# cerebro5_8.net
KiCad netlist of a schematic drawn in EAGLE
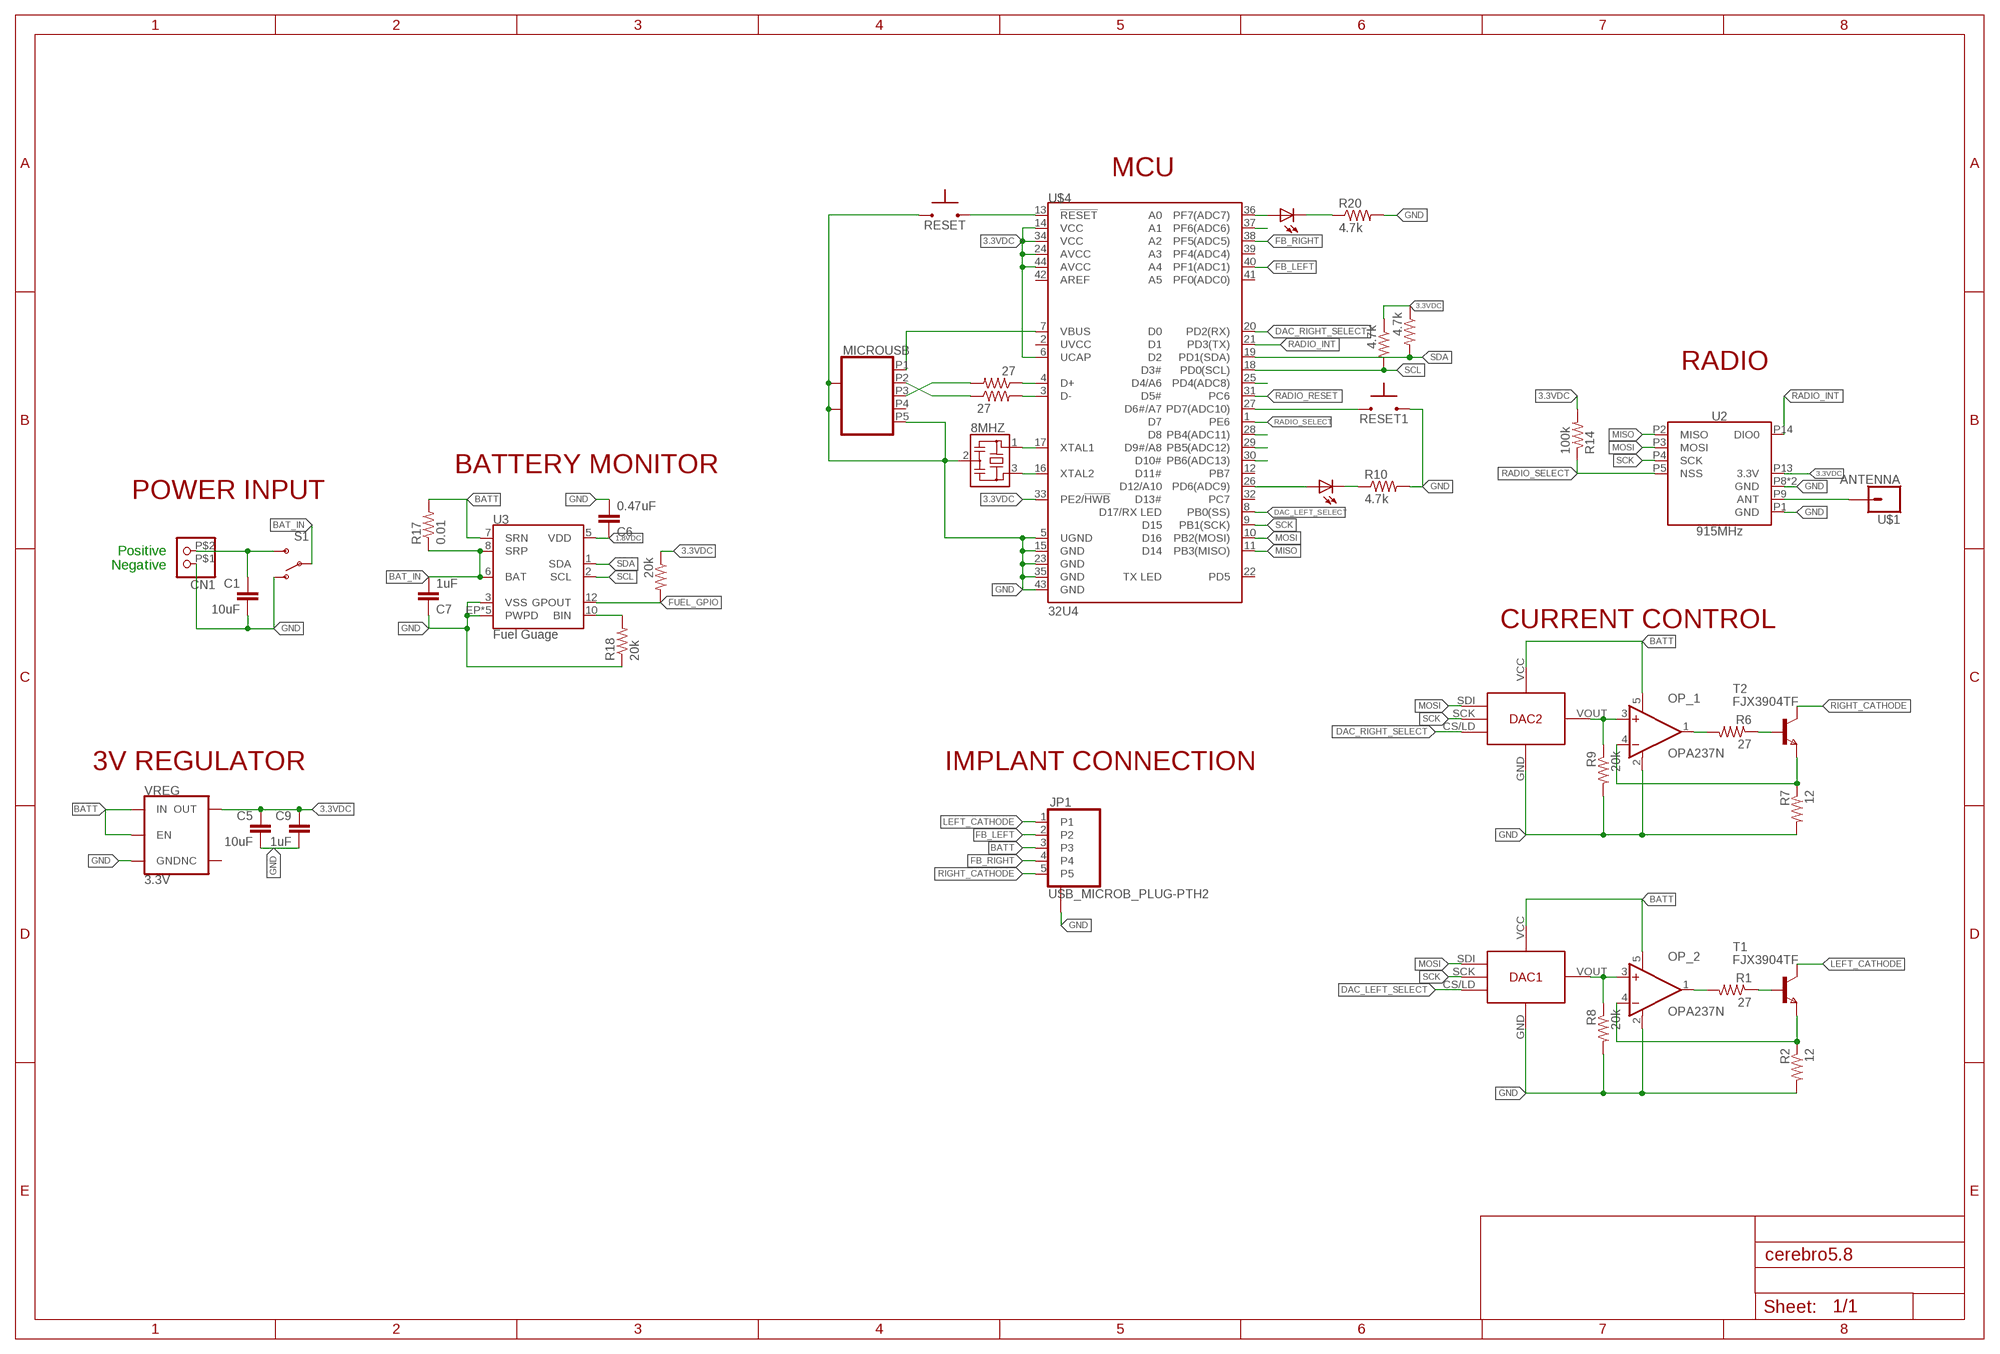
[diagram p0: schematic, sheet 1]

(export (version "E")
  (design (tool "Eeschema 10.0.6"))
  (components
    (comp (ref "8MHZ")
      (value "RESONATOR_CSTCE_V")
      (footprint "eagle-import:CSTCE_V")
      (libsource (lib "eagle-import") (part "RESONATOR_CSTCE_V"))
    )
    (comp (ref "C1")
      (value "10uF")
      (footprint "eagle-import:0805")
      (libsource (lib "eagle-import") (part "10UF-0805-10V-10%"))
    )
    (comp (ref "C5")
      (value "10uF")
      (footprint "eagle-import:0805")
      (libsource (lib "eagle-import") (part "10UF-0805-10V-10%"))
    )
    (comp (ref "C6")
      (value "0.47uF")
      (footprint "eagle-import:0805")
      (libsource (lib "eagle-import") (part "10UF-0805-10V-10%"))
    )
    (comp (ref "C7")
      (value "1uF")
      (footprint "eagle-import:0805")
      (libsource (lib "eagle-import") (part "10UF-0805-10V-10%"))
    )
    (comp (ref "C9")
      (value "1uF")
      (footprint "eagle-import:0805")
      (libsource (lib "eagle-import") (part "10UF-0805-10V-10%"))
    )
    (comp (ref "CN1")
      (value "JST_2PINMICRO")
      (footprint "eagle-import:MICRO_LOCK_2PIN")
      (libsource (lib "eagle-import") (part "JST_2PINMICRO"))
    )
    (comp (ref "DAC1")
      (value "DAC")
      (footprint "eagle-import:SC-70")
      (libsource (lib "eagle-import") (part "DAC_LTC2630"))
    )
    (comp (ref "DAC2")
      (value "DAC")
      (footprint "eagle-import:SC-70")
      (libsource (lib "eagle-import") (part "DAC_LTC2630"))
    )
    (comp (ref "INDICATOR_LED1")
      (value "YLW")
      (footprint "eagle-import:CHIP-LED0603")
      (libsource (lib "eagle-import") (part "LEDCHIP-LED0603"))
    )
    (comp (ref "INDICATOR_LED2")
      (value "GRN")
      (footprint "eagle-import:CHIP-LED0603")
      (libsource (lib "eagle-import") (part "LEDCHIP-LED0603"))
    )
    (comp (ref "JP1")
      (value "USB_MICROB_PLUG-PTH2")
      (footprint "eagle-import:MICRO-B-TH")
      (libsource (lib "eagle-import") (part "USB_MICROB_PLUG-PTH2"))
    )
    (comp (ref "MICROUSB")
      (value "USB_MICRO_SOCKET_HORZ_REINFORCED")
      (footprint "eagle-import:USB_HORZ_REINFORCED_MICRO")
      (libsource (lib "eagle-import") (part "USB_MICRO_SOCKET_HORZ_REINFORCED"))
    )
    (comp (ref "OP_1")
      (value "OPA237N")
      (footprint "eagle-import:SOT23-5")
      (fields (field (name "MF") "TEXAS INSTRUMENTS") (field (name "MPN") "OPA237NA/250"))
      (libsource (lib "eagle-import") (part "OPA237N"))
    )
    (comp (ref "OP_2")
      (value "OPA237N")
      (footprint "eagle-import:SOT23-5")
      (fields (field (name "MF") "TEXAS INSTRUMENTS") (field (name "MPN") "OPA237NA/250"))
      (libsource (lib "eagle-import") (part "OPA237N"))
    )
    (comp (ref "R1")
      (value "27")
      (footprint "eagle-import:0603-RES")
      (libsource (lib "eagle-import") (part "RESISTOR0603-RES"))
    )
    (comp (ref "R2")
      (value "12")
      (footprint "eagle-import:0603-RES")
      (libsource (lib "eagle-import") (part "RESISTOR0603-RES"))
    )
    (comp (ref "R6")
      (value "27")
      (footprint "eagle-import:0603-RES")
      (libsource (lib "eagle-import") (part "RESISTOR0603-RES"))
    )
    (comp (ref "R7")
      (value "12")
      (footprint "eagle-import:0603-RES")
      (libsource (lib "eagle-import") (part "RESISTOR0603-RES"))
    )
    (comp (ref "R8")
      (value "20k")
      (footprint "eagle-import:0603-RES")
      (libsource (lib "eagle-import") (part "RESISTOR0603-RES"))
    )
    (comp (ref "R9")
      (value "20k")
      (footprint "eagle-import:0603-RES")
      (libsource (lib "eagle-import") (part "RESISTOR0603-RES"))
    )
    (comp (ref "R10")
      (value "4.7k")
      (footprint "eagle-import:0603-RES")
      (libsource (lib "eagle-import") (part "RESISTOR0603-RES"))
    )
    (comp (ref "R12")
      (value "27")
      (footprint "eagle-import:0603-RES")
      (libsource (lib "eagle-import") (part "RESISTOR0603-RES"))
    )
    (comp (ref "R13")
      (value "27")
      (footprint "eagle-import:0603-RES")
      (libsource (lib "eagle-import") (part "RESISTOR0603-RES"))
    )
    (comp (ref "R14")
      (value "100k")
      (footprint "eagle-import:0603-RES")
      (libsource (lib "eagle-import") (part "RESISTOR0603-RES"))
    )
    (comp (ref "R15")
      (value "4.7k")
      (footprint "eagle-import:0603-RES")
      (libsource (lib "eagle-import") (part "RESISTOR0603-RES"))
    )
    (comp (ref "R16")
      (value "4.7k")
      (footprint "eagle-import:0603-RES")
      (libsource (lib "eagle-import") (part "RESISTOR0603-RES"))
    )
    (comp (ref "R17")
      (value "0.01")
      (footprint "eagle-import:1206")
      (libsource (lib "eagle-import") (part "RESISTOR1206"))
    )
    (comp (ref "R18")
      (value "20k")
      (footprint "eagle-import:0603-RES")
      (libsource (lib "eagle-import") (part "RESISTOR0603-RES"))
    )
    (comp (ref "R19")
      (value "20k")
      (footprint "eagle-import:0603-RES")
      (libsource (lib "eagle-import") (part "RESISTOR0603-RES"))
    )
    (comp (ref "R20")
      (value "4.7k")
      (footprint "eagle-import:0603-RES")
      (libsource (lib "eagle-import") (part "RESISTOR0603-RES"))
    )
    (comp (ref "RESET")
      (value "SWITCH-MOMENTARY-NO")
      (footprint "eagle-import:SWITCH_MOMENTARY_XS")
      (libsource (lib "eagle-import") (part "SWITCH-MOMENTARY-NO"))
    )
    (comp (ref "RESET1")
      (value "SWITCH-MOMENTARY-NO")
      (footprint "eagle-import:SWITCH_MOMENTARY_XS")
      (libsource (lib "eagle-import") (part "SWITCH-MOMENTARY-NO"))
    )
    (comp (ref "S1")
      (value "SWITCH-SPDTREINFORCED_SMD")
      (footprint "eagle-import:SWITCH-SPDT-SMD-REINFORCED")
      (libsource (lib "eagle-import") (part "SWITCH-SPDTREINFORCED_SMD"))
    )
    (comp (ref "T1")
      (value "FJX3904TF")
      (footprint "eagle-import:SOT323")
      (fields (field (name "MPN") "DSS4160U-7"))
      (libsource (lib "eagle-import") (part "NPNSOT323"))
    )
    (comp (ref "T2")
      (value "FJX3904TF")
      (footprint "eagle-import:SOT323")
      (fields (field (name "MPN") "DSS4160U-7"))
      (libsource (lib "eagle-import") (part "NPNSOT323"))
    )
    (comp (ref "U$1")
      (value "ANTENNA")
      (footprint "eagle-import:1X01")
      (libsource (lib "eagle-import") (part "ANTENNA"))
    )
    (comp (ref "U$4")
      (value "32U4")
      (footprint "eagle-import:QFN-44-NOPAD")
      (libsource (lib "eagle-import") (part "ATMEGA32U4QFN2"))
    )
    (comp (ref "U2")
      (value "915MHz")
      (footprint "eagle-import:RFM69HCW-XXXS2")
      (libsource (lib "eagle-import") (part "RFM69HCW-915"))
    )
    (comp (ref "U3")
      (value "Fuel Guage")
      (footprint "eagle-import:PDSO-N12")
      (libsource (lib "eagle-import") (part "BQ27441-G1"))
    )
    (comp (ref "VREG")
      (value "3.3V")
      (footprint "eagle-import:SOT23-5")
      (libsource (lib "eagle-import") (part "V_REG_AP2112K-3.3V"))
    )
  )
  (nets
    (net (code "1") (name "1.8VDC") (class "Default")
      (node (ref "C6") (pin "1") (pinfunction "1_1") (pintype "passive"))
      (node (ref "U3") (pin "5") (pinfunction "VDD_5") (pintype "bidirectional"))
    )
    (net (code "2") (name "3.3VDC") (class "Default")
      (node (ref "C5") (pin "1") (pinfunction "1_1") (pintype "passive"))
      (node (ref "C9") (pin "1") (pinfunction "1_1") (pintype "passive"))
      (node (ref "R14") (pin "2") (pinfunction "2_2") (pintype "passive"))
      (node (ref "R15") (pin "1") (pinfunction "1_1") (pintype "passive"))
      (node (ref "R16") (pin "1") (pinfunction "1_1") (pintype "passive"))
      (node (ref "R19") (pin "1") (pinfunction "1_1") (pintype "passive"))
      (node (ref "U$4") (pin "14") (pinfunction "VCC_14") (pintype "bidirectional"))
      (node (ref "U$4") (pin "24") (pinfunction "AVCC_24") (pintype "bidirectional"))
      (node (ref "U$4") (pin "33") (pinfunction "PE2/~{HWB}_33") (pintype "bidirectional"))
      (node (ref "U$4") (pin "34") (pinfunction "VCC_34") (pintype "bidirectional"))
      (node (ref "U$4") (pin "44") (pinfunction "AVCC_44") (pintype "bidirectional"))
      (node (ref "U$4") (pin "6") (pinfunction "UCAP_6") (pintype "bidirectional"))
      (node (ref "U2") (pin "P13") (pinfunction "3.3V_P13") (pintype "power_in"))
      (node (ref "VREG") (pin "5") (pinfunction "OUT_5") (pintype "passive"))
    )
    (net (code "3") (name "BATT") (class "Default")
      (node (ref "DAC1") (pin "VCC") (pinfunction "VIN_VCC") (pintype "bidirectional"))
      (node (ref "DAC2") (pin "VCC") (pinfunction "VIN_VCC") (pintype "bidirectional"))
      (node (ref "JP1") (pin "3") (pinfunction "P3_3") (pintype "bidirectional"))
      (node (ref "OP_1") (pin "5") (pinfunction "V+_5") (pintype "power_in"))
      (node (ref "OP_2") (pin "5") (pinfunction "V+_5") (pintype "power_in"))
      (node (ref "R17") (pin "2") (pinfunction "2_2") (pintype "passive"))
      (node (ref "U3") (pin "7") (pinfunction "SRN_7") (pintype "bidirectional"))
      (node (ref "VREG") (pin "1") (pinfunction "IN_1") (pintype "input"))
      (node (ref "VREG") (pin "3") (pinfunction "EN_3") (pintype "input"))
    )
    (net (code "4") (name "BAT_IN") (class "Default")
      (node (ref "C7") (pin "2") (pinfunction "2_2") (pintype "passive"))
      (node (ref "R17") (pin "1") (pinfunction "1_1") (pintype "passive"))
      (node (ref "S1") (pin "2") (pinfunction "P_2") (pintype "passive"))
      (node (ref "U3") (pin "6") (pinfunction "BAT_6") (pintype "bidirectional"))
      (node (ref "U3") (pin "8") (pinfunction "SRP_8") (pintype "bidirectional"))
    )
    (net (code "5") (name "DAC_LEFT_SELECT") (class "Default")
      (node (ref "DAC1") (pin "CS/LD") (pinfunction "CS/LD_CS/LD") (pintype "bidirectional"))
      (node (ref "U$4") (pin "8") (pinfunction "PB0(SS)_8") (pintype "bidirectional"))
    )
    (net (code "6") (name "DAC_RIGHT_SELECT") (class "Default")
      (node (ref "DAC2") (pin "CS/LD") (pinfunction "CS/LD_CS/LD") (pintype "bidirectional"))
      (node (ref "U$4") (pin "20") (pinfunction "PD2(RX)_20") (pintype "bidirectional"))
    )
    (net (code "7") (name "FB_LEFT") (class "Default")
      (node (ref "JP1") (pin "2") (pinfunction "P2_2") (pintype "bidirectional"))
      (node (ref "U$4") (pin "40") (pinfunction "PF1(ADC1)_40") (pintype "bidirectional"))
    )
    (net (code "8") (name "FB_RIGHT") (class "Default")
      (node (ref "JP1") (pin "4") (pinfunction "P4_4") (pintype "bidirectional"))
      (node (ref "U$4") (pin "38") (pinfunction "PF5(ADC5)_38") (pintype "bidirectional"))
    )
    (net (code "9") (name "FUEL_GPIO") (class "Default")
      (node (ref "R19") (pin "2") (pinfunction "2_2") (pintype "passive"))
      (node (ref "U3") (pin "12") (pinfunction "GPOUT_12") (pintype "bidirectional"))
    )
    (net (code "10") (name "GND") (class "Default")
      (node (ref "8MHZ") (pin "2") (pinfunction "2_2") (pintype "passive"))
      (node (ref "C1") (pin "2") (pinfunction "2_2") (pintype "passive"))
      (node (ref "C5") (pin "2") (pinfunction "2_2") (pintype "passive"))
      (node (ref "C6") (pin "2") (pinfunction "2_2") (pintype "passive"))
      (node (ref "C7") (pin "1") (pinfunction "1_1") (pintype "passive"))
      (node (ref "C9") (pin "2") (pinfunction "2_2") (pintype "passive"))
      (node (ref "CN1") (pin "P$1") (pinfunction "1_P$1") (pintype "passive"))
      (node (ref "DAC1") (pin "GND") (pinfunction "GND_GND") (pintype "bidirectional"))
      (node (ref "DAC2") (pin "GND") (pinfunction "GND_GND") (pintype "bidirectional"))
      (node (ref "JP1") (pin "P$1") (pinfunction "GND_PINS_P$1") (pintype "bidirectional"))
      (node (ref "JP1") (pin "P$2") (pinfunction "GND_PINS_P$2") (pintype "bidirectional"))
      (node (ref "MICROUSB") (pin "G1") (pinfunction "P$1_G1") (pintype "bidirectional"))
      (node (ref "MICROUSB") (pin "G2") (pinfunction "P$1_G2") (pintype "bidirectional"))
      (node (ref "MICROUSB") (pin "P$1") (pinfunction "P$2_P$1") (pintype "bidirectional"))
      (node (ref "MICROUSB") (pin "P$2") (pinfunction "P$2_P$2") (pintype "bidirectional"))
      (node (ref "MICROUSB") (pin "P5") (pinfunction "P5_P5") (pintype "bidirectional"))
      (node (ref "OP_1") (pin "2") (pinfunction "V-_2") (pintype "power_in"))
      (node (ref "OP_2") (pin "2") (pinfunction "V-_2") (pintype "power_in"))
      (node (ref "R10") (pin "2") (pinfunction "2_2") (pintype "passive"))
      (node (ref "R18") (pin "1") (pinfunction "1_1") (pintype "passive"))
      (node (ref "R2") (pin "2") (pinfunction "2_2") (pintype "passive"))
      (node (ref "R20") (pin "2") (pinfunction "2_2") (pintype "passive"))
      (node (ref "R7") (pin "2") (pinfunction "2_2") (pintype "passive"))
      (node (ref "R8") (pin "2") (pinfunction "2_2") (pintype "passive"))
      (node (ref "R9") (pin "2") (pinfunction "2_2") (pintype "passive"))
      (node (ref "RESET") (pin "P$1") (pinfunction "1_P$1") (pintype "bidirectional"))
      (node (ref "RESET1") (pin "P$2") (pinfunction "2_P$2") (pintype "bidirectional"))
      (node (ref "S1") (pin "1") (pinfunction "O_1") (pintype "passive"))
      (node (ref "U$4") (pin "15") (pinfunction "GND_15") (pintype "bidirectional"))
      (node (ref "U$4") (pin "23") (pinfunction "GND_23") (pintype "bidirectional"))
      (node (ref "U$4") (pin "35") (pinfunction "GND_35") (pintype "bidirectional"))
      (node (ref "U$4") (pin "43") (pinfunction "GND_43") (pintype "bidirectional"))
      (node (ref "U$4") (pin "5") (pinfunction "UGND_5") (pintype "bidirectional"))
      (node (ref "U2") (pin "P1") (pinfunction "GND_P1") (pintype "power_in"))
      (node (ref "U2") (pin "P10") (pinfunction "GND_P10") (pintype "power_in"))
      (node (ref "U2") (pin "P8") (pinfunction "GND_P8") (pintype "power_in"))
      (node (ref "U3") (pin "3") (pinfunction "VSS_3") (pintype "bidirectional"))
      (node (ref "U3") (pin "EP") (pinfunction "PWPD_EP") (pintype "bidirectional"))
      (node (ref "U3") (pin "EP1") (pinfunction "PWPD_EP1") (pintype "bidirectional"))
      (node (ref "U3") (pin "EP2") (pinfunction "PWPD_EP2") (pintype "bidirectional"))
      (node (ref "U3") (pin "EP3") (pinfunction "PWPD_EP3") (pintype "bidirectional"))
      (node (ref "U3") (pin "EP4") (pinfunction "PWPD_EP4") (pintype "bidirectional"))
      (node (ref "VREG") (pin "2") (pinfunction "GND_2") (pintype "input"))
    )
    (net (code "11") (name "LEFT_CATHODE") (class "Default")
      (node (ref "JP1") (pin "1") (pinfunction "P1_1") (pintype "bidirectional"))
      (node (ref "T1") (pin "1") (pinfunction "C_1") (pintype "passive"))
    )
    (net (code "12") (name "MISO") (class "Default")
      (node (ref "U$4") (pin "11") (pinfunction "PB3(MISO)_11") (pintype "bidirectional"))
      (node (ref "U2") (pin "P2") (pinfunction "MISO_P2") (pintype "bidirectional"))
    )
    (net (code "13") (name "MOSI") (class "Default")
      (node (ref "DAC1") (pin "SDI") (pinfunction "SDI_SDI") (pintype "bidirectional"))
      (node (ref "DAC2") (pin "SDI") (pinfunction "SDI_SDI") (pintype "bidirectional"))
      (node (ref "U$4") (pin "10") (pinfunction "PB2(MOSI)_10") (pintype "bidirectional"))
      (node (ref "U2") (pin "P3") (pinfunction "MOSI_P3") (pintype "input"))
    )
    (net (code "14") (name "Net-(CN1-2)") (class "Default")
      (node (ref "C1") (pin "1") (pinfunction "1_1") (pintype "passive"))
      (node (ref "CN1") (pin "P$2") (pinfunction "2_P$2") (pintype "passive"))
      (node (ref "S1") (pin "3") (pinfunction "S_3") (pintype "passive"))
    )
    (net (code "15") (name "Net-(INDICATOR_LED1-PadC)") (class "Default")
      (node (ref "INDICATOR_LED1") (pin "C") (pinfunction "C_C") (pintype "passive"))
      (node (ref "R20") (pin "1") (pinfunction "1_1") (pintype "passive"))
    )
    (net (code "16") (name "Net-(INDICATOR_LED2-PadC)") (class "Default")
      (node (ref "INDICATOR_LED2") (pin "C") (pinfunction "C_C") (pintype "passive"))
      (node (ref "R10") (pin "1") (pinfunction "1_1") (pintype "passive"))
    )
    (net (code "17") (name "Net-(MICROUSB-PadP2)") (class "Default")
      (node (ref "MICROUSB") (pin "P2") (pinfunction "P2_P2") (pintype "bidirectional"))
      (node (ref "R13") (pin "1") (pinfunction "1_1") (pintype "passive"))
    )
    (net (code "18") (name "Net-(MICROUSB-PadP3)") (class "Default")
      (node (ref "MICROUSB") (pin "P3") (pinfunction "P3_P3") (pintype "bidirectional"))
      (node (ref "R12") (pin "2") (pinfunction "2_2") (pintype "passive"))
    )
    (net (code "19") (name "Net-(OP_1-+IN)") (class "Default")
      (node (ref "DAC2") (pin "VOUT") (pinfunction "VOUT_VOUT") (pintype "bidirectional"))
      (node (ref "OP_1") (pin "3") (pinfunction "+IN_3") (pintype "input"))
      (node (ref "R9") (pin "1") (pinfunction "1_1") (pintype "passive"))
    )
    (net (code "20") (name "Net-(OP_1--IN)") (class "Default")
      (node (ref "OP_1") (pin "4") (pinfunction "-IN_4") (pintype "input"))
      (node (ref "R7") (pin "1") (pinfunction "1_1") (pintype "passive"))
      (node (ref "T2") (pin "3") (pinfunction "E_3") (pintype "passive"))
    )
    (net (code "21") (name "Net-(OP_1-OUT)") (class "Default")
      (node (ref "OP_1") (pin "1") (pinfunction "OUT_1") (pintype "output"))
      (node (ref "R6") (pin "2") (pinfunction "2_2") (pintype "passive"))
    )
    (net (code "22") (name "Net-(OP_2-+IN)") (class "Default")
      (node (ref "DAC1") (pin "VOUT") (pinfunction "VOUT_VOUT") (pintype "bidirectional"))
      (node (ref "OP_2") (pin "3") (pinfunction "+IN_3") (pintype "input"))
      (node (ref "R8") (pin "1") (pinfunction "1_1") (pintype "passive"))
    )
    (net (code "23") (name "Net-(OP_2--IN)") (class "Default")
      (node (ref "OP_2") (pin "4") (pinfunction "-IN_4") (pintype "input"))
      (node (ref "R2") (pin "1") (pinfunction "1_1") (pintype "passive"))
      (node (ref "T1") (pin "3") (pinfunction "E_3") (pintype "passive"))
    )
    (net (code "24") (name "Net-(OP_2-OUT)") (class "Default")
      (node (ref "OP_2") (pin "1") (pinfunction "OUT_1") (pintype "output"))
      (node (ref "R1") (pin "2") (pinfunction "2_2") (pintype "passive"))
    )
    (net (code "25") (name "Net-(RESET-2)") (class "Default")
      (node (ref "RESET") (pin "P$2") (pinfunction "2_P$2") (pintype "bidirectional"))
      (node (ref "U$4") (pin "13") (pinfunction "~{RESET}_13") (pintype "bidirectional"))
    )
    (net (code "26") (name "Net-(RESET1-1)") (class "Default")
      (node (ref "RESET1") (pin "P$1") (pinfunction "1_P$1") (pintype "bidirectional"))
      (node (ref "U$4") (pin "27") (pinfunction "PD7(ADC10)_27") (pintype "bidirectional"))
    )
    (net (code "27") (name "Net-(T1-B)") (class "Default")
      (node (ref "R1") (pin "1") (pinfunction "1_1") (pintype "passive"))
      (node (ref "T1") (pin "2") (pinfunction "B_2") (pintype "passive"))
    )
    (net (code "28") (name "Net-(T2-B)") (class "Default")
      (node (ref "R6") (pin "1") (pinfunction "1_1") (pintype "passive"))
      (node (ref "T2") (pin "2") (pinfunction "B_2") (pintype "passive"))
    )
    (net (code "29") (name "Net-(U$4-D+)") (class "Default")
      (node (ref "R12") (pin "1") (pinfunction "1_1") (pintype "passive"))
      (node (ref "U$4") (pin "4") (pinfunction "D+_4") (pintype "bidirectional"))
    )
    (net (code "30") (name "Net-(U$4-D-)") (class "Default")
      (node (ref "R13") (pin "2") (pinfunction "2_2") (pintype "passive"))
      (node (ref "U$4") (pin "3") (pinfunction "D-_3") (pintype "bidirectional"))
    )
    (net (code "31") (name "Net-(U$4-PD6(ADC9))") (class "Default")
      (node (ref "INDICATOR_LED2") (pin "A") (pinfunction "A_A") (pintype "passive"))
      (node (ref "U$4") (pin "26") (pinfunction "PD6(ADC9)_26") (pintype "bidirectional"))
    )
    (net (code "32") (name "Net-(U$4-PF7(ADC7))") (class "Default")
      (node (ref "INDICATOR_LED1") (pin "A") (pinfunction "A_A") (pintype "passive"))
      (node (ref "U$4") (pin "36") (pinfunction "PF7(ADC7)_36") (pintype "bidirectional"))
    )
    (net (code "33") (name "Net-(U$4-VBUS)") (class "Default")
      (node (ref "MICROUSB") (pin "P1") (pinfunction "P1_P1") (pintype "bidirectional"))
      (node (ref "U$4") (pin "7") (pinfunction "VBUS_7") (pintype "bidirectional"))
    )
    (net (code "34") (name "Net-(U$4-XTAL1)") (class "Default")
      (node (ref "8MHZ") (pin "1") (pinfunction "1_1") (pintype "passive"))
      (node (ref "U$4") (pin "17") (pinfunction "XTAL1_17") (pintype "bidirectional"))
    )
    (net (code "35") (name "Net-(U$4-XTAL2)") (class "Default")
      (node (ref "8MHZ") (pin "3") (pinfunction "3_3") (pintype "passive"))
      (node (ref "U$4") (pin "16") (pinfunction "XTAL2_16") (pintype "bidirectional"))
    )
    (net (code "36") (name "Net-(U2-ANT)") (class "Default")
      (node (ref "U$1") (pin "1") (pinfunction "1_1") (pintype "passive"))
      (node (ref "U2") (pin "P9") (pinfunction "ANT_P9") (pintype "passive"))
    )
    (net (code "37") (name "Net-(U3-BIN)") (class "Default")
      (node (ref "R18") (pin "2") (pinfunction "2_2") (pintype "passive"))
      (node (ref "U3") (pin "10") (pinfunction "BIN_10") (pintype "bidirectional"))
    )
    (net (code "38") (name "RADIO_INT") (class "Default")
      (node (ref "U$4") (pin "21") (pinfunction "PD3(TX)_21") (pintype "bidirectional"))
      (node (ref "U2") (pin "P14") (pinfunction "DIO0_P14") (pintype "bidirectional"))
    )
    (net (code "39") (name "RADIO_RESET") (class "Default")
      (node (ref "U$4") (pin "31") (pinfunction "PC6_31") (pintype "bidirectional"))
    )
    (net (code "40") (name "RADIO_SELECT") (class "Default")
      (node (ref "R14") (pin "1") (pinfunction "1_1") (pintype "passive"))
      (node (ref "U$4") (pin "1") (pinfunction "PE6_1") (pintype "bidirectional"))
      (node (ref "U2") (pin "P5") (pinfunction "NSS_P5") (pintype "input"))
    )
    (net (code "41") (name "RIGHT_CATHODE") (class "Default")
      (node (ref "JP1") (pin "5") (pinfunction "P5_5") (pintype "bidirectional"))
      (node (ref "T2") (pin "1") (pinfunction "C_1") (pintype "passive"))
    )
    (net (code "42") (name "SCK") (class "Default")
      (node (ref "DAC1") (pin "SCK") (pinfunction "SCK_SCK") (pintype "bidirectional"))
      (node (ref "DAC2") (pin "SCK") (pinfunction "SCK_SCK") (pintype "bidirectional"))
      (node (ref "U$4") (pin "9") (pinfunction "PB1(SCK)_9") (pintype "bidirectional"))
      (node (ref "U2") (pin "P4") (pinfunction "SCK_P4") (pintype "input"))
    )
    (net (code "43") (name "SCL") (class "Default")
      (node (ref "R15") (pin "2") (pinfunction "2_2") (pintype "passive"))
      (node (ref "U$4") (pin "18") (pinfunction "PD0(SCL)_18") (pintype "bidirectional"))
      (node (ref "U3") (pin "2") (pinfunction "SCL_2") (pintype "bidirectional"))
    )
    (net (code "44") (name "SDA") (class "Default")
      (node (ref "R16") (pin "2") (pinfunction "2_2") (pintype "passive"))
      (node (ref "U$4") (pin "19") (pinfunction "PD1(SDA)_19") (pintype "bidirectional"))
      (node (ref "U3") (pin "1") (pinfunction "SDA_1") (pintype "bidirectional"))
    )
    (net (code "45") (name "unconnected-(MICROUSB-PadP4)") (class "Default")
      (node (ref "MICROUSB") (pin "P4") (pinfunction "P4_P4") (pintype "bidirectional"))
    )
    (net (code "46") (name "unconnected-(U$4-AREF-Pad42)") (class "Default")
      (node (ref "U$4") (pin "42") (pinfunction "AREF_42") (pintype "bidirectional"))
    )
    (net (code "47") (name "unconnected-(U$4-PB4(ADC11)-Pad28)") (class "Default")
      (node (ref "U$4") (pin "28") (pinfunction "PB4(ADC11)_28") (pintype "bidirectional"))
    )
    (net (code "48") (name "unconnected-(U$4-PB5(ADC12)-Pad29)") (class "Default")
      (node (ref "U$4") (pin "29") (pinfunction "PB5(ADC12)_29") (pintype "bidirectional"))
    )
    (net (code "49") (name "unconnected-(U$4-PB6(ADC13)-Pad30)") (class "Default")
      (node (ref "U$4") (pin "30") (pinfunction "PB6(ADC13)_30") (pintype "bidirectional"))
    )
    (net (code "50") (name "unconnected-(U$4-PB7-Pad12)") (class "Default")
      (node (ref "U$4") (pin "12") (pinfunction "PB7_12") (pintype "bidirectional"))
    )
    (net (code "51") (name "unconnected-(U$4-PC7-Pad32)") (class "Default")
      (node (ref "U$4") (pin "32") (pinfunction "PC7_32") (pintype "bidirectional"))
    )
    (net (code "52") (name "unconnected-(U$4-PD4(ADC8)-Pad25)") (class "Default")
      (node (ref "U$4") (pin "25") (pinfunction "PD4(ADC8)_25") (pintype "bidirectional"))
    )
    (net (code "53") (name "unconnected-(U$4-PD5-Pad22)") (class "Default")
      (node (ref "U$4") (pin "22") (pinfunction "PD5_22") (pintype "bidirectional"))
    )
    (net (code "54") (name "unconnected-(U$4-PF0(ADC0)-Pad41)") (class "Default")
      (node (ref "U$4") (pin "41") (pinfunction "PF0(ADC0)_41") (pintype "bidirectional"))
    )
    (net (code "55") (name "unconnected-(U$4-PF4(ADC4)-Pad39)") (class "Default")
      (node (ref "U$4") (pin "39") (pinfunction "PF4(ADC4)_39") (pintype "bidirectional"))
    )
    (net (code "56") (name "unconnected-(U$4-PF6(ADC6)-Pad37)") (class "Default")
      (node (ref "U$4") (pin "37") (pinfunction "PF6(ADC6)_37") (pintype "bidirectional"))
    )
    (net (code "57") (name "unconnected-(U$4-UVCC-Pad2)") (class "Default")
      (node (ref "U$4") (pin "2") (pinfunction "UVCC_2") (pintype "bidirectional"))
    )
    (net (code "58") (name "unconnected-(VREG-NC-Pad4)") (class "Default")
      (node (ref "VREG") (pin "4") (pinfunction "NC_4") (pintype "no_connect"))
    )
  )
)
